# Headlightsv4_1.net
KiCad netlist of a schematic drawn in EAGLE
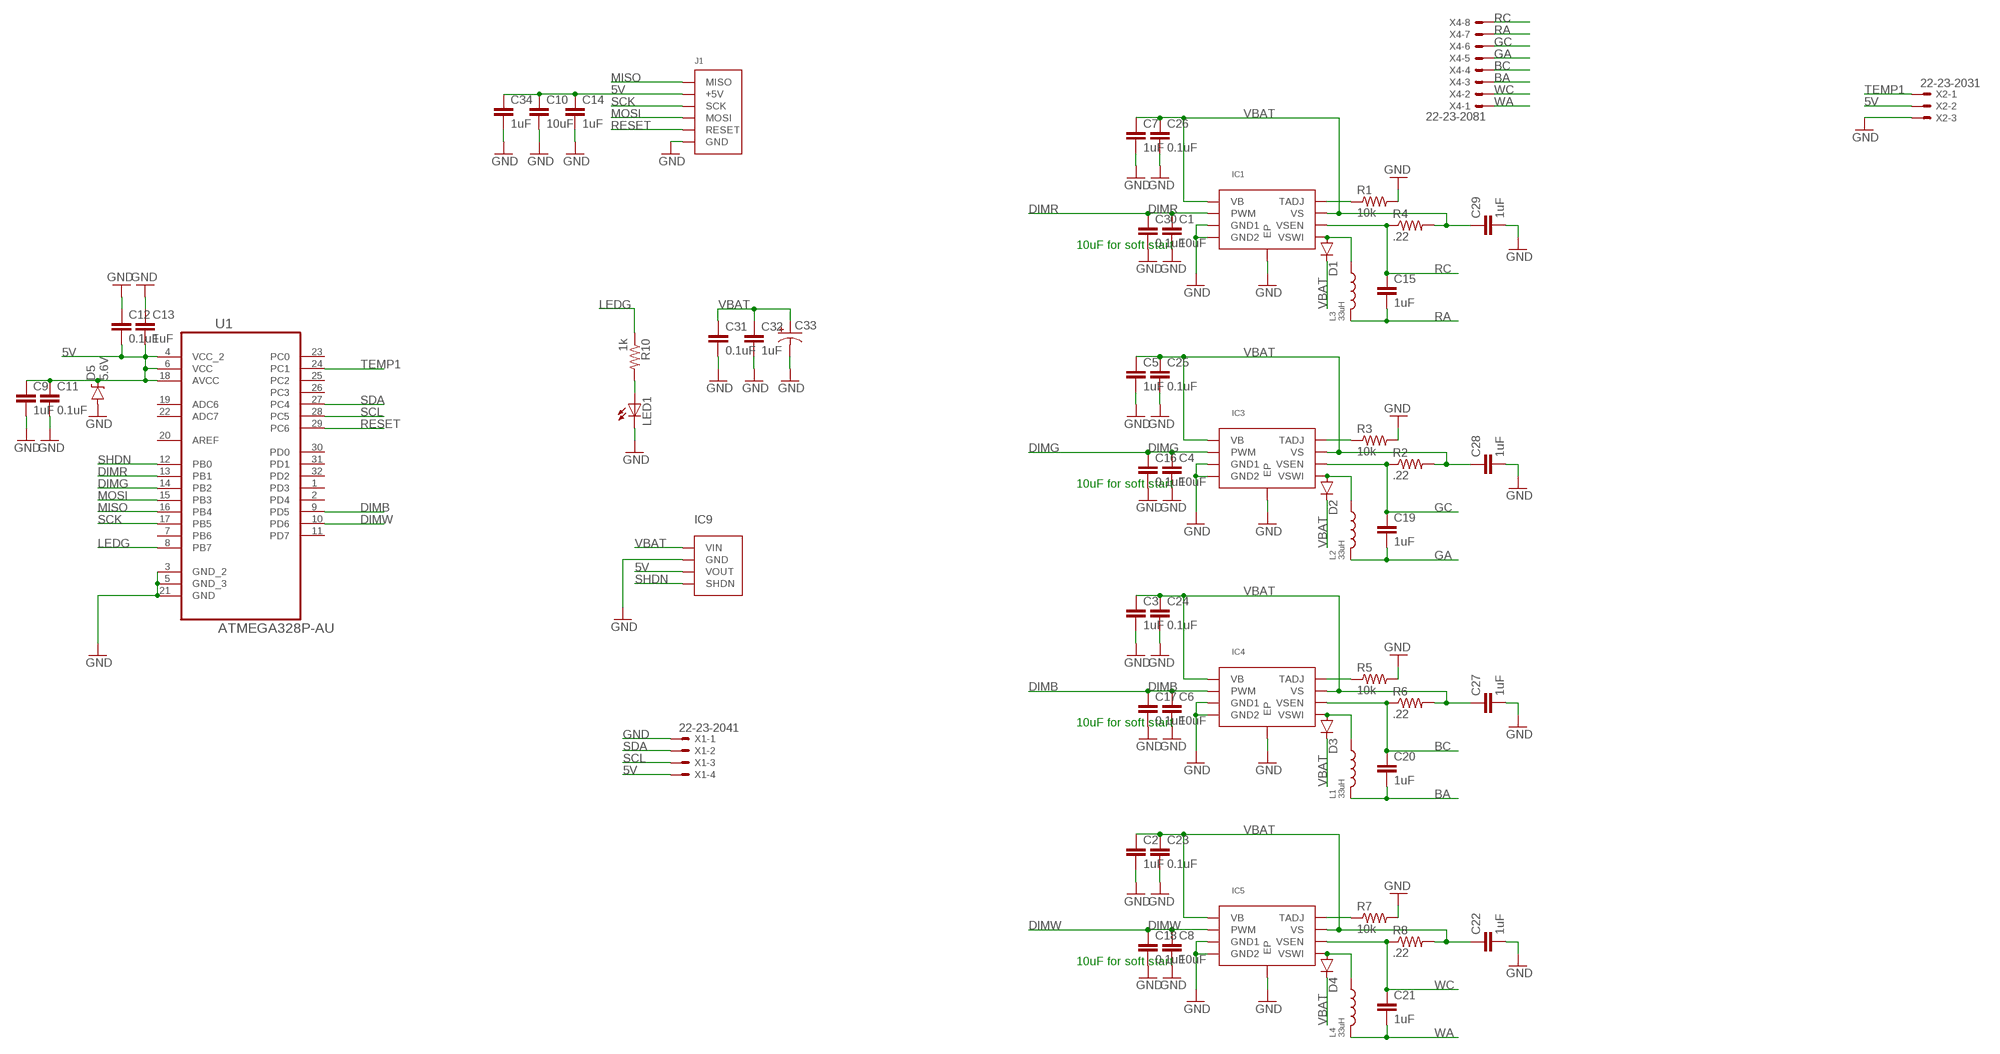
[diagram p0: schematic, sheet 1]

(export (version "E")
  (design (tool "Eeschema 10.0.6"))
  (components
    (comp (ref "C1")
      (value "10uF")
      (footprint "eagle-import:0805-CAP")
      (libsource (lib "eagle-import") (part "10UF10V10%(0805)"))
    )
    (comp (ref "C2")
      (value "1uF")
      (footprint "eagle-import:0805-CAP")
      (libsource (lib "eagle-import") (part "0.33UF-50V-10%(0805)"))
    )
    (comp (ref "C3")
      (value "1uF")
      (footprint "eagle-import:0805-CAP")
      (libsource (lib "eagle-import") (part "0.33UF-50V-10%(0805)"))
    )
    (comp (ref "C4")
      (value "10uF")
      (footprint "eagle-import:0805-CAP")
      (libsource (lib "eagle-import") (part "10UF10V10%(0805)"))
    )
    (comp (ref "C5")
      (value "1uF")
      (footprint "eagle-import:0805-CAP")
      (libsource (lib "eagle-import") (part "0.33UF-50V-10%(0805)"))
    )
    (comp (ref "C6")
      (value "10uF")
      (footprint "eagle-import:0805-CAP")
      (libsource (lib "eagle-import") (part "10UF10V10%(0805)"))
    )
    (comp (ref "C7")
      (value "1uF")
      (footprint "eagle-import:0805-CAP")
      (libsource (lib "eagle-import") (part "0.33UF-50V-10%(0805)"))
    )
    (comp (ref "C8")
      (value "10uF")
      (footprint "eagle-import:0805-CAP")
      (libsource (lib "eagle-import") (part "10UF10V10%(0805)"))
    )
    (comp (ref "C9")
      (value "1uF")
      (footprint "eagle-import:0805-CAP")
      (libsource (lib "eagle-import") (part "0.33UF-50V-10%(0805)"))
    )
    (comp (ref "C10")
      (value "10uF")
      (footprint "eagle-import:0805-CAP")
      (libsource (lib "eagle-import") (part "10UF10V10%(0805)"))
    )
    (comp (ref "C11")
      (value "0.1uF")
      (footprint "eagle-import:0805-CAP")
      (libsource (lib "eagle-import") (part "0.33UF-50V-10%(0805)"))
    )
    (comp (ref "C12")
      (value "0.1uF")
      (footprint "eagle-import:0805-CAP")
      (libsource (lib "eagle-import") (part "0.33UF-50V-10%(0805)"))
    )
    (comp (ref "C13")
      (value "1uF")
      (footprint "eagle-import:0805-CAP")
      (libsource (lib "eagle-import") (part "0.33UF-50V-10%(0805)"))
    )
    (comp (ref "C14")
      (value "1uF")
      (footprint "eagle-import:0805-CAP")
      (libsource (lib "eagle-import") (part "0.33UF-50V-10%(0805)"))
    )
    (comp (ref "C15")
      (value "1uF")
      (footprint "eagle-import:0805-CAP")
      (libsource (lib "eagle-import") (part "0.33UF-50V-10%(0805)"))
    )
    (comp (ref "C16")
      (value "0.1uF")
      (footprint "eagle-import:0805-CAP")
      (libsource (lib "eagle-import") (part "0.33UF-50V-10%(0805)"))
    )
    (comp (ref "C17")
      (value "0.1uF")
      (footprint "eagle-import:0805-CAP")
      (libsource (lib "eagle-import") (part "0.33UF-50V-10%(0805)"))
    )
    (comp (ref "C18")
      (value "0.1uF")
      (footprint "eagle-import:0805-CAP")
      (libsource (lib "eagle-import") (part "0.33UF-50V-10%(0805)"))
    )
    (comp (ref "C19")
      (value "1uF")
      (footprint "eagle-import:0805-CAP")
      (libsource (lib "eagle-import") (part "0.33UF-50V-10%(0805)"))
    )
    (comp (ref "C20")
      (value "1uF")
      (footprint "eagle-import:0805-CAP")
      (libsource (lib "eagle-import") (part "0.33UF-50V-10%(0805)"))
    )
    (comp (ref "C21")
      (value "1uF")
      (footprint "eagle-import:0805-CAP")
      (libsource (lib "eagle-import") (part "0.33UF-50V-10%(0805)"))
    )
    (comp (ref "C22")
      (value "1uF")
      (footprint "eagle-import:0805-CAP")
      (libsource (lib "eagle-import") (part "0.33UF-50V-10%(0805)"))
    )
    (comp (ref "C23")
      (value "0.1uF")
      (footprint "eagle-import:0805-CAP")
      (libsource (lib "eagle-import") (part "0.33UF-50V-10%(0805)"))
    )
    (comp (ref "C24")
      (value "0.1uF")
      (footprint "eagle-import:0805-CAP")
      (libsource (lib "eagle-import") (part "0.33UF-50V-10%(0805)"))
    )
    (comp (ref "C25")
      (value "0.1uF")
      (footprint "eagle-import:0805-CAP")
      (libsource (lib "eagle-import") (part "0.33UF-50V-10%(0805)"))
    )
    (comp (ref "C26")
      (value "0.1uF")
      (footprint "eagle-import:0805-CAP")
      (libsource (lib "eagle-import") (part "0.33UF-50V-10%(0805)"))
    )
    (comp (ref "C27")
      (value "1uF")
      (footprint "eagle-import:0805-CAP")
      (libsource (lib "eagle-import") (part "0.33UF-50V-10%(0805)"))
    )
    (comp (ref "C28")
      (value "1uF")
      (footprint "eagle-import:0805-CAP")
      (libsource (lib "eagle-import") (part "0.33UF-50V-10%(0805)"))
    )
    (comp (ref "C29")
      (value "1uF")
      (footprint "eagle-import:0805-CAP")
      (libsource (lib "eagle-import") (part "0.33UF-50V-10%(0805)"))
    )
    (comp (ref "C30")
      (value "0.1uF")
      (footprint "eagle-import:0805-CAP")
      (libsource (lib "eagle-import") (part "0.33UF-50V-10%(0805)"))
    )
    (comp (ref "C31")
      (value "0.1uF")
      (footprint "eagle-import:0805-CAP")
      (libsource (lib "eagle-import") (part "0.33UF-50V-10%(0805)"))
    )
    (comp (ref "C32")
      (value "1uF")
      (footprint "eagle-import:0805-CAP")
      (libsource (lib "eagle-import") (part "0.33UF-50V-10%(0805)"))
    )
    (comp (ref "C33")
      (value "CAP_POLF80")
      (footprint "eagle-import:NIPPON_F80")
      (libsource (lib "eagle-import") (part "CAP_POLF80"))
    )
    (comp (ref "C34")
      (value "1uF")
      (footprint "eagle-import:0805-CAP")
      (libsource (lib "eagle-import") (part "0.33UF-50V-10%(0805)"))
    )
    (comp (ref "D1")
      (value "DIODESMA-ALT")
      (footprint "eagle-import:SMA-DIODE_ALT")
      (libsource (lib "eagle-import") (part "DIODESMA-ALT"))
    )
    (comp (ref "D2")
      (value "DIODESMA-ALT")
      (footprint "eagle-import:SMA-DIODE_ALT")
      (libsource (lib "eagle-import") (part "DIODESMA-ALT"))
    )
    (comp (ref "D3")
      (value "DIODESMA-ALT")
      (footprint "eagle-import:SMA-DIODE_ALT")
      (libsource (lib "eagle-import") (part "DIODESMA-ALT"))
    )
    (comp (ref "D4")
      (value "DIODESMA-ALT")
      (footprint "eagle-import:SMA-DIODE_ALT")
      (libsource (lib "eagle-import") (part "DIODESMA-ALT"))
    )
    (comp (ref "D5")
      (value "5.6V")
      (footprint "eagle-import:SOD-323")
      (libsource (lib "eagle-import") (part "DIODE-ZENER5.6V"))
    )
    (comp (ref "IC1")
      (value "ILD6150_LED_DRIVER")
      (footprint "eagle-import:PG-DSO-8-27")
      (libsource (lib "eagle-import") (part "ILD6150_LED_DRIVER"))
    )
    (comp (ref "IC3")
      (value "ILD6150_LED_DRIVER")
      (footprint "eagle-import:PG-DSO-8-27")
      (libsource (lib "eagle-import") (part "ILD6150_LED_DRIVER"))
    )
    (comp (ref "IC4")
      (value "ILD6150_LED_DRIVER")
      (footprint "eagle-import:PG-DSO-8-27")
      (libsource (lib "eagle-import") (part "ILD6150_LED_DRIVER"))
    )
    (comp (ref "IC5")
      (value "ILD6150_LED_DRIVER")
      (footprint "eagle-import:PG-DSO-8-27")
      (libsource (lib "eagle-import") (part "ILD6150_LED_DRIVER"))
    )
    (comp (ref "IC9")
      (value "5VBUCK_DANNY_CUSTOM_PCB")
      (footprint "eagle-import:4PIN_.1'")
      (libsource (lib "eagle-import") (part "5VBUCK_DANNY_CUSTOM_PCB"))
    )
    (comp (ref "J1")
      (value "ISPHEADER")
      (footprint "eagle-import:2X3PIN_.1'")
      (libsource (lib "eagle-import") (part "ISPHEADER"))
    )
    (comp (ref "L1")
      (value "33uH")
      (footprint "eagle-import:8X8MM_IND")
      (libsource (lib "eagle-import") (part "CHIP_IND"))
    )
    (comp (ref "L2")
      (value "33uH")
      (footprint "eagle-import:8X8MM_IND")
      (libsource (lib "eagle-import") (part "CHIP_IND"))
    )
    (comp (ref "L3")
      (value "33uH")
      (footprint "eagle-import:8X8MM_IND")
      (libsource (lib "eagle-import") (part "CHIP_IND"))
    )
    (comp (ref "L4")
      (value "33uH")
      (footprint "eagle-import:8X8MM_IND")
      (libsource (lib "eagle-import") (part "CHIP_IND"))
    )
    (comp (ref "LED1")
      (value "LEDCHIPLED_0805")
      (footprint "eagle-import:CHIPLED_0805")
      (libsource (lib "eagle-import") (part "LEDCHIPLED_0805"))
    )
    (comp (ref "R1")
      (value "10k")
      (footprint "eagle-import:0805")
      (libsource (lib "eagle-import") (part "0.3OHM-1/8W-1%(0805)"))
    )
    (comp (ref "R2")
      (value ".22")
      (footprint "eagle-import:1206")
      (libsource (lib "eagle-import") (part "RESISTOR1206"))
    )
    (comp (ref "R3")
      (value "10k")
      (footprint "eagle-import:0805")
      (libsource (lib "eagle-import") (part "0.3OHM-1/8W-1%(0805)"))
    )
    (comp (ref "R4")
      (value ".22")
      (footprint "eagle-import:1206")
      (libsource (lib "eagle-import") (part "RESISTOR1206"))
    )
    (comp (ref "R5")
      (value "10k")
      (footprint "eagle-import:0805")
      (libsource (lib "eagle-import") (part "0.3OHM-1/8W-1%(0805)"))
    )
    (comp (ref "R6")
      (value ".22")
      (footprint "eagle-import:1206")
      (libsource (lib "eagle-import") (part "RESISTOR1206"))
    )
    (comp (ref "R7")
      (value "10k")
      (footprint "eagle-import:0805")
      (libsource (lib "eagle-import") (part "0.3OHM-1/8W-1%(0805)"))
    )
    (comp (ref "R8")
      (value ".22")
      (footprint "eagle-import:1206")
      (libsource (lib "eagle-import") (part "RESISTOR1206"))
    )
    (comp (ref "R10")
      (value "1k")
      (footprint "eagle-import:0805")
      (libsource (lib "eagle-import") (part "0.3OHM-1/8W-1%(0805)"))
    )
    (comp (ref "U1")
      (value "ATMEGA328P-AU")
      (footprint "eagle-import:QFP80P900X900X120-32N")
      (libsource (lib "eagle-import") (part "ATMEGA328P-AU"))
    )
    (comp (ref "X1")
      (value "22-23-2041")
      (footprint "eagle-import:22-23-2041")
      (fields (field (name "MF") "MOLEX"))
      (libsource (lib "eagle-import") (part "22-23-2041"))
    )
    (comp (ref "X2")
      (value "22-23-2031")
      (footprint "eagle-import:22-23-2031")
      (fields (field (name "MF") "MOLEX"))
      (libsource (lib "eagle-import") (part "22-23-2031"))
    )
    (comp (ref "X4")
      (value "22-23-2081")
      (footprint "eagle-import:22-23-2081")
      (fields (field (name "MF") "MOLEX"))
      (libsource (lib "eagle-import") (part "22-23-2081"))
    )
  )
  (nets
    (net (code "1") (name "/5V") (class "Default")
      (node (ref "C10") (pin "1") (pinfunction "1_1") (pintype "passive"))
      (node (ref "C11") (pin "1") (pinfunction "1_1") (pintype "passive"))
      (node (ref "C12") (pin "2") (pinfunction "2_2") (pintype "passive"))
      (node (ref "C13") (pin "2") (pinfunction "2_2") (pintype "passive"))
      (node (ref "C14") (pin "1") (pinfunction "1_1") (pintype "passive"))
      (node (ref "C34") (pin "1") (pinfunction "1_1") (pintype "passive"))
      (node (ref "C9") (pin "1") (pinfunction "1_1") (pintype "passive"))
      (node (ref "D5") (pin "C") (pinfunction "C_C") (pintype "passive"))
      (node (ref "IC9") (pin "P$3") (pinfunction "VOUT_P$3") (pintype "bidirectional"))
      (node (ref "J1") (pin "P$2") (pinfunction "+5V_P$2") (pintype "bidirectional"))
      (node (ref "U1") (pin "18") (pinfunction "AVCC_18") (pintype "power_in"))
      (node (ref "U1") (pin "4") (pinfunction "VCC_2_4") (pintype "power_in"))
      (node (ref "U1") (pin "6") (pinfunction "VCC_6") (pintype "power_in"))
      (node (ref "X1") (pin "4") (pinfunction "S_4") (pintype "passive"))
      (node (ref "X2") (pin "2") (pinfunction "S_2") (pintype "passive"))
    )
    (net (code "2") (name "/BA") (class "Default")
      (node (ref "C20") (pin "2") (pinfunction "2_2") (pintype "passive"))
      (node (ref "L1") (pin "P$1") (pinfunction "P$1_P$1") (pintype "bidirectional"))
      (node (ref "X4") (pin "3") (pinfunction "S_3") (pintype "passive"))
    )
    (net (code "3") (name "/BC") (class "Default")
      (node (ref "C20") (pin "1") (pinfunction "1_1") (pintype "passive"))
      (node (ref "IC4") (pin "P$6") (pinfunction "VSEN_P$6") (pintype "bidirectional"))
      (node (ref "R6") (pin "1") (pinfunction "1_1") (pintype "passive"))
      (node (ref "X4") (pin "4") (pinfunction "S_4") (pintype "passive"))
    )
    (net (code "4") (name "/DIMB") (class "Default")
      (node (ref "C17") (pin "1") (pinfunction "1_1") (pintype "passive"))
      (node (ref "C6") (pin "1") (pinfunction "1_1") (pintype "passive"))
      (node (ref "IC4") (pin "P$2") (pinfunction "PWM_P$2") (pintype "bidirectional"))
      (node (ref "U1") (pin "9") (pinfunction "PD5_9") (pintype "bidirectional"))
    )
    (net (code "5") (name "/DIMG") (class "Default")
      (node (ref "C16") (pin "1") (pinfunction "1_1") (pintype "passive"))
      (node (ref "C4") (pin "1") (pinfunction "1_1") (pintype "passive"))
      (node (ref "IC3") (pin "P$2") (pinfunction "PWM_P$2") (pintype "bidirectional"))
      (node (ref "U1") (pin "14") (pinfunction "PB2_14") (pintype "bidirectional"))
    )
    (net (code "6") (name "/DIMR") (class "Default")
      (node (ref "C1") (pin "1") (pinfunction "1_1") (pintype "passive"))
      (node (ref "C30") (pin "1") (pinfunction "1_1") (pintype "passive"))
      (node (ref "IC1") (pin "P$2") (pinfunction "PWM_P$2") (pintype "bidirectional"))
      (node (ref "U1") (pin "13") (pinfunction "PB1_13") (pintype "bidirectional"))
    )
    (net (code "7") (name "/DIMW") (class "Default")
      (node (ref "C18") (pin "1") (pinfunction "1_1") (pintype "passive"))
      (node (ref "C8") (pin "1") (pinfunction "1_1") (pintype "passive"))
      (node (ref "IC5") (pin "P$2") (pinfunction "PWM_P$2") (pintype "bidirectional"))
      (node (ref "U1") (pin "10") (pinfunction "PD6_10") (pintype "bidirectional"))
    )
    (net (code "8") (name "/GA") (class "Default")
      (node (ref "C19") (pin "2") (pinfunction "2_2") (pintype "passive"))
      (node (ref "L2") (pin "P$1") (pinfunction "P$1_P$1") (pintype "bidirectional"))
      (node (ref "X4") (pin "5") (pinfunction "S_5") (pintype "passive"))
    )
    (net (code "9") (name "/GC") (class "Default")
      (node (ref "C19") (pin "1") (pinfunction "1_1") (pintype "passive"))
      (node (ref "IC3") (pin "P$6") (pinfunction "VSEN_P$6") (pintype "bidirectional"))
      (node (ref "R2") (pin "1") (pinfunction "1_1") (pintype "passive"))
      (node (ref "X4") (pin "6") (pinfunction "S_6") (pintype "passive"))
    )
    (net (code "10") (name "/LEDG") (class "Default")
      (node (ref "R10") (pin "1") (pinfunction "1_1") (pintype "passive"))
      (node (ref "U1") (pin "8") (pinfunction "PB7_8") (pintype "bidirectional"))
    )
    (net (code "11") (name "/MISO") (class "Default")
      (node (ref "J1") (pin "P$1") (pinfunction "MISO_P$1") (pintype "bidirectional"))
      (node (ref "U1") (pin "16") (pinfunction "PB4_16") (pintype "bidirectional"))
    )
    (net (code "12") (name "/MOSI") (class "Default")
      (node (ref "J1") (pin "P$4") (pinfunction "MOSI_P$4") (pintype "bidirectional"))
      (node (ref "U1") (pin "15") (pinfunction "PB3_15") (pintype "bidirectional"))
    )
    (net (code "13") (name "/RA") (class "Default")
      (node (ref "C15") (pin "2") (pinfunction "2_2") (pintype "passive"))
      (node (ref "L3") (pin "P$1") (pinfunction "P$1_P$1") (pintype "bidirectional"))
      (node (ref "X4") (pin "7") (pinfunction "S_7") (pintype "passive"))
    )
    (net (code "14") (name "/RC") (class "Default")
      (node (ref "C15") (pin "1") (pinfunction "1_1") (pintype "passive"))
      (node (ref "IC1") (pin "P$6") (pinfunction "VSEN_P$6") (pintype "bidirectional"))
      (node (ref "R4") (pin "1") (pinfunction "1_1") (pintype "passive"))
      (node (ref "X4") (pin "8") (pinfunction "S_8") (pintype "passive"))
    )
    (net (code "15") (name "/RESET") (class "Default")
      (node (ref "J1") (pin "P$5") (pinfunction "RESET_P$5") (pintype "bidirectional"))
      (node (ref "U1") (pin "29") (pinfunction "PC6_29") (pintype "bidirectional"))
    )
    (net (code "16") (name "/SCK") (class "Default")
      (node (ref "J1") (pin "P$3") (pinfunction "SCK_P$3") (pintype "bidirectional"))
      (node (ref "U1") (pin "17") (pinfunction "PB5_17") (pintype "bidirectional"))
    )
    (net (code "17") (name "/SCL") (class "Default")
      (node (ref "U1") (pin "28") (pinfunction "PC5_28") (pintype "bidirectional"))
      (node (ref "X1") (pin "3") (pinfunction "S_3") (pintype "passive"))
    )
    (net (code "18") (name "/SDA") (class "Default")
      (node (ref "U1") (pin "27") (pinfunction "PC4_27") (pintype "bidirectional"))
      (node (ref "X1") (pin "2") (pinfunction "S_2") (pintype "passive"))
    )
    (net (code "19") (name "/SHDN") (class "Default")
      (node (ref "IC9") (pin "P$4") (pinfunction "SHDN_P$4") (pintype "bidirectional"))
      (node (ref "U1") (pin "12") (pinfunction "PB0_12") (pintype "bidirectional"))
    )
    (net (code "20") (name "/TEMP1") (class "Default")
      (node (ref "U1") (pin "24") (pinfunction "PC1_24") (pintype "bidirectional"))
      (node (ref "X2") (pin "1") (pinfunction "S_1") (pintype "passive"))
    )
    (net (code "21") (name "/VBAT") (class "Default")
      (node (ref "C2") (pin "1") (pinfunction "1_1") (pintype "passive"))
      (node (ref "C22") (pin "1") (pinfunction "1_1") (pintype "passive"))
      (node (ref "C23") (pin "1") (pinfunction "1_1") (pintype "passive"))
      (node (ref "C24") (pin "1") (pinfunction "1_1") (pintype "passive"))
      (node (ref "C25") (pin "1") (pinfunction "1_1") (pintype "passive"))
      (node (ref "C26") (pin "1") (pinfunction "1_1") (pintype "passive"))
      (node (ref "C27") (pin "1") (pinfunction "1_1") (pintype "passive"))
      (node (ref "C28") (pin "1") (pinfunction "1_1") (pintype "passive"))
      (node (ref "C29") (pin "1") (pinfunction "1_1") (pintype "passive"))
      (node (ref "C3") (pin "1") (pinfunction "1_1") (pintype "passive"))
      (node (ref "C31") (pin "1") (pinfunction "1_1") (pintype "passive"))
      (node (ref "C32") (pin "1") (pinfunction "1_1") (pintype "passive"))
      (node (ref "C33") (pin "+") (pinfunction "+_+") (pintype "passive"))
      (node (ref "C5") (pin "1") (pinfunction "1_1") (pintype "passive"))
      (node (ref "C7") (pin "1") (pinfunction "1_1") (pintype "passive"))
      (node (ref "D1") (pin "C") (pinfunction "C_C") (pintype "passive"))
      (node (ref "D2") (pin "C") (pinfunction "C_C") (pintype "passive"))
      (node (ref "D3") (pin "C") (pinfunction "C_C") (pintype "passive"))
      (node (ref "D4") (pin "C") (pinfunction "C_C") (pintype "passive"))
      (node (ref "IC1") (pin "P$1") (pinfunction "VB_P$1") (pintype "bidirectional"))
      (node (ref "IC1") (pin "P$7") (pinfunction "VS_P$7") (pintype "bidirectional"))
      (node (ref "IC3") (pin "P$1") (pinfunction "VB_P$1") (pintype "bidirectional"))
      (node (ref "IC3") (pin "P$7") (pinfunction "VS_P$7") (pintype "bidirectional"))
      (node (ref "IC4") (pin "P$1") (pinfunction "VB_P$1") (pintype "bidirectional"))
      (node (ref "IC4") (pin "P$7") (pinfunction "VS_P$7") (pintype "bidirectional"))
      (node (ref "IC5") (pin "P$1") (pinfunction "VB_P$1") (pintype "bidirectional"))
      (node (ref "IC5") (pin "P$7") (pinfunction "VS_P$7") (pintype "bidirectional"))
      (node (ref "IC9") (pin "P$1") (pinfunction "VIN_P$1") (pintype "bidirectional"))
      (node (ref "R2") (pin "2") (pinfunction "2_2") (pintype "passive"))
      (node (ref "R4") (pin "2") (pinfunction "2_2") (pintype "passive"))
      (node (ref "R6") (pin "2") (pinfunction "2_2") (pintype "passive"))
      (node (ref "R8") (pin "2") (pinfunction "2_2") (pintype "passive"))
    )
    (net (code "22") (name "/WA") (class "Default")
      (node (ref "C21") (pin "2") (pinfunction "2_2") (pintype "passive"))
      (node (ref "L4") (pin "P$1") (pinfunction "P$1_P$1") (pintype "bidirectional"))
      (node (ref "X4") (pin "1") (pinfunction "S_1") (pintype "passive"))
    )
    (net (code "23") (name "/WC") (class "Default")
      (node (ref "C21") (pin "1") (pinfunction "1_1") (pintype "passive"))
      (node (ref "IC5") (pin "P$6") (pinfunction "VSEN_P$6") (pintype "bidirectional"))
      (node (ref "R8") (pin "1") (pinfunction "1_1") (pintype "passive"))
      (node (ref "X4") (pin "2") (pinfunction "S_2") (pintype "passive"))
    )
    (net (code "24") (name "GND") (class "Default")
      (node (ref "C1") (pin "2") (pinfunction "2_2") (pintype "passive"))
      (node (ref "C10") (pin "2") (pinfunction "2_2") (pintype "passive"))
      (node (ref "C11") (pin "2") (pinfunction "2_2") (pintype "passive"))
      (node (ref "C12") (pin "1") (pinfunction "1_1") (pintype "passive"))
      (node (ref "C13") (pin "1") (pinfunction "1_1") (pintype "passive"))
      (node (ref "C14") (pin "2") (pinfunction "2_2") (pintype "passive"))
      (node (ref "C16") (pin "2") (pinfunction "2_2") (pintype "passive"))
      (node (ref "C17") (pin "2") (pinfunction "2_2") (pintype "passive"))
      (node (ref "C18") (pin "2") (pinfunction "2_2") (pintype "passive"))
      (node (ref "C2") (pin "2") (pinfunction "2_2") (pintype "passive"))
      (node (ref "C22") (pin "2") (pinfunction "2_2") (pintype "passive"))
      (node (ref "C23") (pin "2") (pinfunction "2_2") (pintype "passive"))
      (node (ref "C24") (pin "2") (pinfunction "2_2") (pintype "passive"))
      (node (ref "C25") (pin "2") (pinfunction "2_2") (pintype "passive"))
      (node (ref "C26") (pin "2") (pinfunction "2_2") (pintype "passive"))
      (node (ref "C27") (pin "2") (pinfunction "2_2") (pintype "passive"))
      (node (ref "C28") (pin "2") (pinfunction "2_2") (pintype "passive"))
      (node (ref "C29") (pin "2") (pinfunction "2_2") (pintype "passive"))
      (node (ref "C3") (pin "2") (pinfunction "2_2") (pintype "passive"))
      (node (ref "C30") (pin "2") (pinfunction "2_2") (pintype "passive"))
      (node (ref "C31") (pin "2") (pinfunction "2_2") (pintype "passive"))
      (node (ref "C32") (pin "2") (pinfunction "2_2") (pintype "passive"))
      (node (ref "C33") (pin "-") (pinfunction "-_-") (pintype "passive"))
      (node (ref "C34") (pin "2") (pinfunction "2_2") (pintype "passive"))
      (node (ref "C4") (pin "2") (pinfunction "2_2") (pintype "passive"))
      (node (ref "C5") (pin "2") (pinfunction "2_2") (pintype "passive"))
      (node (ref "C6") (pin "2") (pinfunction "2_2") (pintype "passive"))
      (node (ref "C7") (pin "2") (pinfunction "2_2") (pintype "passive"))
      (node (ref "C8") (pin "2") (pinfunction "2_2") (pintype "passive"))
      (node (ref "C9") (pin "2") (pinfunction "2_2") (pintype "passive"))
      (node (ref "D5") (pin "A") (pinfunction "A_A") (pintype "passive"))
      (node (ref "IC1") (pin "P$3") (pinfunction "GND1_P$3") (pintype "bidirectional"))
      (node (ref "IC1") (pin "P$4") (pinfunction "GND2_P$4") (pintype "bidirectional"))
      (node (ref "IC1") (pin "P$9") (pinfunction "EP_P$9") (pintype "bidirectional"))
      (node (ref "IC3") (pin "P$3") (pinfunction "GND1_P$3") (pintype "bidirectional"))
      (node (ref "IC3") (pin "P$4") (pinfunction "GND2_P$4") (pintype "bidirectional"))
      (node (ref "IC3") (pin "P$9") (pinfunction "EP_P$9") (pintype "bidirectional"))
      (node (ref "IC4") (pin "P$3") (pinfunction "GND1_P$3") (pintype "bidirectional"))
      (node (ref "IC4") (pin "P$4") (pinfunction "GND2_P$4") (pintype "bidirectional"))
      (node (ref "IC4") (pin "P$9") (pinfunction "EP_P$9") (pintype "bidirectional"))
      (node (ref "IC5") (pin "P$3") (pinfunction "GND1_P$3") (pintype "bidirectional"))
      (node (ref "IC5") (pin "P$4") (pinfunction "GND2_P$4") (pintype "bidirectional"))
      (node (ref "IC5") (pin "P$9") (pinfunction "EP_P$9") (pintype "bidirectional"))
      (node (ref "IC9") (pin "P$2") (pinfunction "GND_P$2") (pintype "bidirectional"))
      (node (ref "J1") (pin "P$6") (pinfunction "GND_P$6") (pintype "bidirectional"))
      (node (ref "LED1") (pin "C") (pinfunction "C_C") (pintype "passive"))
      (node (ref "R1") (pin "2") (pinfunction "2_2") (pintype "passive"))
      (node (ref "R3") (pin "2") (pinfunction "2_2") (pintype "passive"))
      (node (ref "R5") (pin "2") (pinfunction "2_2") (pintype "passive"))
      (node (ref "R7") (pin "2") (pinfunction "2_2") (pintype "passive"))
      (node (ref "U1") (pin "21") (pinfunction "GND_21") (pintype "passive"))
      (node (ref "U1") (pin "3") (pinfunction "GND_2_3") (pintype "passive"))
      (node (ref "U1") (pin "5") (pinfunction "GND_3_5") (pintype "passive"))
      (node (ref "X1") (pin "1") (pinfunction "S_1") (pintype "passive"))
      (node (ref "X2") (pin "3") (pinfunction "S_3") (pintype "passive"))
    )
    (net (code "25") (name "Net-(IC1-TADJ)") (class "Default")
      (node (ref "IC1") (pin "P$8") (pinfunction "TADJ_P$8") (pintype "bidirectional"))
      (node (ref "R1") (pin "1") (pinfunction "1_1") (pintype "passive"))
    )
    (net (code "26") (name "Net-(IC1-VSWI)") (class "Default")
      (node (ref "D1") (pin "A") (pinfunction "A_A") (pintype "passive"))
      (node (ref "IC1") (pin "P$5") (pinfunction "VSWI_P$5") (pintype "bidirectional"))
      (node (ref "L3") (pin "P$2") (pinfunction "P$2_P$2") (pintype "bidirectional"))
    )
    (net (code "27") (name "Net-(IC3-TADJ)") (class "Default")
      (node (ref "IC3") (pin "P$8") (pinfunction "TADJ_P$8") (pintype "bidirectional"))
      (node (ref "R3") (pin "1") (pinfunction "1_1") (pintype "passive"))
    )
    (net (code "28") (name "Net-(IC3-VSWI)") (class "Default")
      (node (ref "D2") (pin "A") (pinfunction "A_A") (pintype "passive"))
      (node (ref "IC3") (pin "P$5") (pinfunction "VSWI_P$5") (pintype "bidirectional"))
      (node (ref "L2") (pin "P$2") (pinfunction "P$2_P$2") (pintype "bidirectional"))
    )
    (net (code "29") (name "Net-(IC4-TADJ)") (class "Default")
      (node (ref "IC4") (pin "P$8") (pinfunction "TADJ_P$8") (pintype "bidirectional"))
      (node (ref "R5") (pin "1") (pinfunction "1_1") (pintype "passive"))
    )
    (net (code "30") (name "Net-(IC4-VSWI)") (class "Default")
      (node (ref "D3") (pin "A") (pinfunction "A_A") (pintype "passive"))
      (node (ref "IC4") (pin "P$5") (pinfunction "VSWI_P$5") (pintype "bidirectional"))
      (node (ref "L1") (pin "P$2") (pinfunction "P$2_P$2") (pintype "bidirectional"))
    )
    (net (code "31") (name "Net-(IC5-TADJ)") (class "Default")
      (node (ref "IC5") (pin "P$8") (pinfunction "TADJ_P$8") (pintype "bidirectional"))
      (node (ref "R7") (pin "1") (pinfunction "1_1") (pintype "passive"))
    )
    (net (code "32") (name "Net-(IC5-VSWI)") (class "Default")
      (node (ref "D4") (pin "A") (pinfunction "A_A") (pintype "passive"))
      (node (ref "IC5") (pin "P$5") (pinfunction "VSWI_P$5") (pintype "bidirectional"))
      (node (ref "L4") (pin "P$2") (pinfunction "P$2_P$2") (pintype "bidirectional"))
    )
    (net (code "33") (name "Net-(LED1-PadA)") (class "Default")
      (node (ref "LED1") (pin "A") (pinfunction "A_A") (pintype "passive"))
      (node (ref "R10") (pin "2") (pinfunction "2_2") (pintype "passive"))
    )
    (net (code "34") (name "unconnected-(U1-ADC6-Pad19)") (class "Default")
      (node (ref "U1") (pin "19") (pinfunction "ADC6_19") (pintype "input"))
    )
    (net (code "35") (name "unconnected-(U1-ADC7-Pad22)") (class "Default")
      (node (ref "U1") (pin "22") (pinfunction "ADC7_22") (pintype "input"))
    )
    (net (code "36") (name "unconnected-(U1-AREF-Pad20)") (class "Default")
      (node (ref "U1") (pin "20") (pinfunction "AREF_20") (pintype "input"))
    )
    (net (code "37") (name "unconnected-(U1-PB6-Pad7)") (class "Default")
      (node (ref "U1") (pin "7") (pinfunction "PB6_7") (pintype "bidirectional"))
    )
    (net (code "38") (name "unconnected-(U1-PC0-Pad23)") (class "Default")
      (node (ref "U1") (pin "23") (pinfunction "PC0_23") (pintype "bidirectional"))
    )
    (net (code "39") (name "unconnected-(U1-PC2-Pad25)") (class "Default")
      (node (ref "U1") (pin "25") (pinfunction "PC2_25") (pintype "bidirectional"))
    )
    (net (code "40") (name "unconnected-(U1-PC3-Pad26)") (class "Default")
      (node (ref "U1") (pin "26") (pinfunction "PC3_26") (pintype "bidirectional"))
    )
    (net (code "41") (name "unconnected-(U1-PD0-Pad30)") (class "Default")
      (node (ref "U1") (pin "30") (pinfunction "PD0_30") (pintype "bidirectional"))
    )
    (net (code "42") (name "unconnected-(U1-PD1-Pad31)") (class "Default")
      (node (ref "U1") (pin "31") (pinfunction "PD1_31") (pintype "bidirectional"))
    )
    (net (code "43") (name "unconnected-(U1-PD2-Pad32)") (class "Default")
      (node (ref "U1") (pin "32") (pinfunction "PD2_32") (pintype "bidirectional"))
    )
    (net (code "44") (name "unconnected-(U1-PD3-Pad1)") (class "Default")
      (node (ref "U1") (pin "1") (pinfunction "PD3_1") (pintype "bidirectional"))
    )
    (net (code "45") (name "unconnected-(U1-PD4-Pad2)") (class "Default")
      (node (ref "U1") (pin "2") (pinfunction "PD4_2") (pintype "bidirectional"))
    )
    (net (code "46") (name "unconnected-(U1-PD7-Pad11)") (class "Default")
      (node (ref "U1") (pin "11") (pinfunction "PD7_11") (pintype "bidirectional"))
    )
  )
)
